# Atari_2006_Dumper.net
KiCad netlist of a schematic drawn in EAGLE
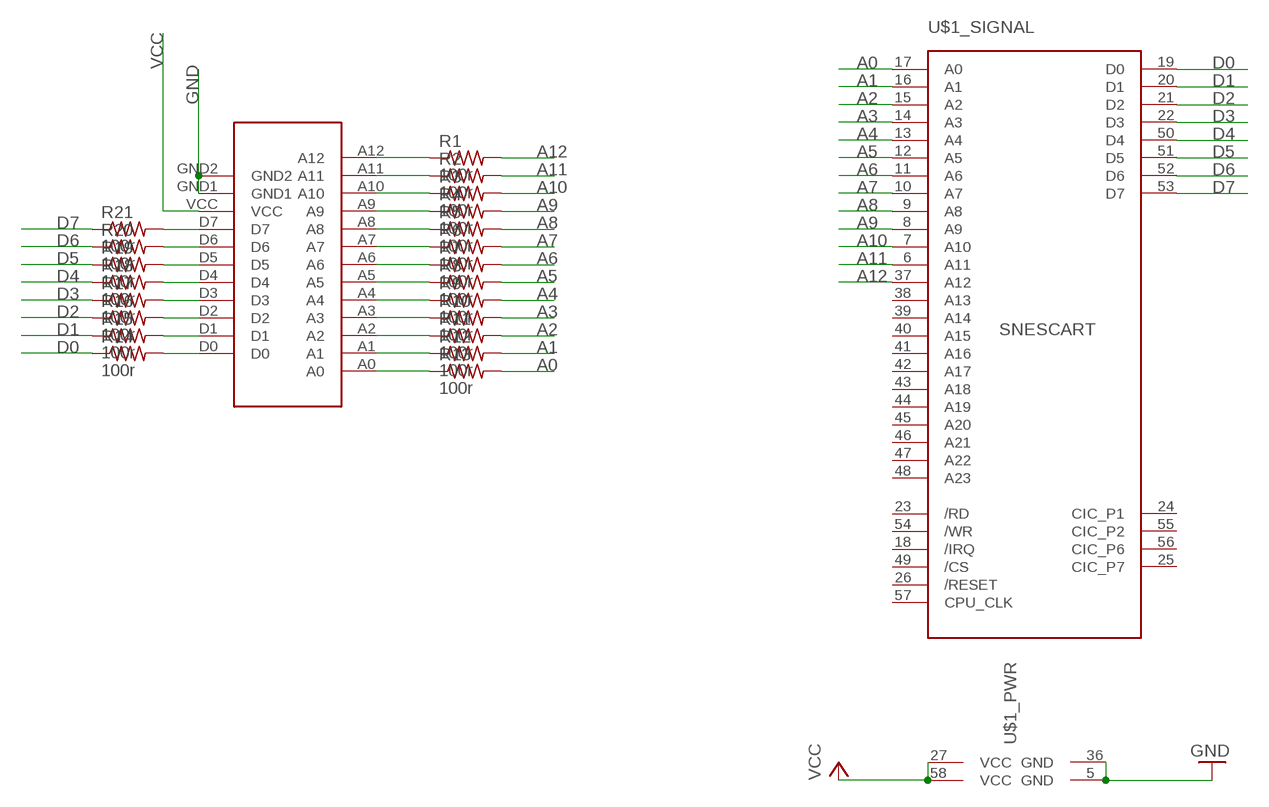
[diagram p0: schematic, sheet 1]

(export (version "E")
  (design (tool "Eeschema 10.0.6"))
  (components
    (comp (ref "R1")
      (value "100r")
      (footprint "eagle-import:R0603")
      (libsource (lib "eagle-import") (part "R-US_R0603"))
    )
    (comp (ref "R2")
      (value "100r")
      (footprint "eagle-import:R0603")
      (libsource (lib "eagle-import") (part "R-US_R0603"))
    )
    (comp (ref "R3")
      (value "100r")
      (footprint "eagle-import:R0603")
      (libsource (lib "eagle-import") (part "R-US_R0603"))
    )
    (comp (ref "R4")
      (value "100r")
      (footprint "eagle-import:R0603")
      (libsource (lib "eagle-import") (part "R-US_R0603"))
    )
    (comp (ref "R5")
      (value "100r")
      (footprint "eagle-import:R0603")
      (libsource (lib "eagle-import") (part "R-US_R0603"))
    )
    (comp (ref "R6")
      (value "100r")
      (footprint "eagle-import:R0603")
      (libsource (lib "eagle-import") (part "R-US_R0603"))
    )
    (comp (ref "R7")
      (value "100r")
      (footprint "eagle-import:R0603")
      (libsource (lib "eagle-import") (part "R-US_R0603"))
    )
    (comp (ref "R8")
      (value "100r")
      (footprint "eagle-import:R0603")
      (libsource (lib "eagle-import") (part "R-US_R0603"))
    )
    (comp (ref "R9")
      (value "100r")
      (footprint "eagle-import:R0603")
      (libsource (lib "eagle-import") (part "R-US_R0603"))
    )
    (comp (ref "R10")
      (value "100r")
      (footprint "eagle-import:R0603")
      (libsource (lib "eagle-import") (part "R-US_R0603"))
    )
    (comp (ref "R11")
      (value "100r")
      (footprint "eagle-import:R0603")
      (libsource (lib "eagle-import") (part "R-US_R0603"))
    )
    (comp (ref "R12")
      (value "100r")
      (footprint "eagle-import:R0603")
      (libsource (lib "eagle-import") (part "R-US_R0603"))
    )
    (comp (ref "R13")
      (value "100r")
      (footprint "eagle-import:R0603")
      (libsource (lib "eagle-import") (part "R-US_R0603"))
    )
    (comp (ref "R14")
      (value "100r")
      (footprint "eagle-import:R0603")
      (libsource (lib "eagle-import") (part "R-US_R0603"))
    )
    (comp (ref "R15")
      (value "100r")
      (footprint "eagle-import:R0603")
      (libsource (lib "eagle-import") (part "R-US_R0603"))
    )
    (comp (ref "R16")
      (value "100r")
      (footprint "eagle-import:R0603")
      (libsource (lib "eagle-import") (part "R-US_R0603"))
    )
    (comp (ref "R17")
      (value "100r")
      (footprint "eagle-import:R0603")
      (libsource (lib "eagle-import") (part "R-US_R0603"))
    )
    (comp (ref "R18")
      (value "100r")
      (footprint "eagle-import:R0603")
      (libsource (lib "eagle-import") (part "R-US_R0603"))
    )
    (comp (ref "R19")
      (value "100r")
      (footprint "eagle-import:R0603")
      (libsource (lib "eagle-import") (part "R-US_R0603"))
    )
    (comp (ref "R20")
      (value "100r")
      (footprint "eagle-import:R0603")
      (libsource (lib "eagle-import") (part "R-US_R0603"))
    )
    (comp (ref "R21")
      (value "100r")
      (footprint "eagle-import:R0603")
      (libsource (lib "eagle-import") (part "R-US_R0603"))
    )
    (comp (ref "U$1")
      (value "SNESCART")
      (footprint "eagle-import:SNESCART")
      (libsource (lib "eagle-import") (part "SNESCART"))
    )
    (comp (ref "U$2")
      (value "2600CARTBIGGERPADS")
      (footprint "eagle-import:2600EDGE-BIGGER")
      (libsource (lib "eagle-import") (part "2600CARTBIGGERPADS"))
    )
  )
  (nets
    (net (code "1") (name "/A0") (class "Default")
      (node (ref "R13") (pin "2") (pinfunction "2_2") (pintype "passive"))
      (node (ref "U$1") (pin "17") (pinfunction "A0_17") (pintype "bidirectional"))
    )
    (net (code "2") (name "/A1") (class "Default")
      (node (ref "R12") (pin "2") (pinfunction "2_2") (pintype "passive"))
      (node (ref "U$1") (pin "16") (pinfunction "A1_16") (pintype "bidirectional"))
    )
    (net (code "3") (name "/A2") (class "Default")
      (node (ref "R11") (pin "2") (pinfunction "2_2") (pintype "passive"))
      (node (ref "U$1") (pin "15") (pinfunction "A2_15") (pintype "bidirectional"))
    )
    (net (code "4") (name "/A3") (class "Default")
      (node (ref "R10") (pin "2") (pinfunction "2_2") (pintype "passive"))
      (node (ref "U$1") (pin "14") (pinfunction "A3_14") (pintype "bidirectional"))
    )
    (net (code "5") (name "/A4") (class "Default")
      (node (ref "R9") (pin "2") (pinfunction "2_2") (pintype "passive"))
      (node (ref "U$1") (pin "13") (pinfunction "A4_13") (pintype "bidirectional"))
    )
    (net (code "6") (name "/A5") (class "Default")
      (node (ref "R8") (pin "2") (pinfunction "2_2") (pintype "passive"))
      (node (ref "U$1") (pin "12") (pinfunction "A5_12") (pintype "bidirectional"))
    )
    (net (code "7") (name "/A6") (class "Default")
      (node (ref "R7") (pin "2") (pinfunction "2_2") (pintype "passive"))
      (node (ref "U$1") (pin "11") (pinfunction "A6_11") (pintype "bidirectional"))
    )
    (net (code "8") (name "/A7") (class "Default")
      (node (ref "R6") (pin "2") (pinfunction "2_2") (pintype "passive"))
      (node (ref "U$1") (pin "10") (pinfunction "A7_10") (pintype "bidirectional"))
    )
    (net (code "9") (name "/A8") (class "Default")
      (node (ref "R5") (pin "2") (pinfunction "2_2") (pintype "passive"))
      (node (ref "U$1") (pin "9") (pinfunction "A8_9") (pintype "bidirectional"))
    )
    (net (code "10") (name "/A9") (class "Default")
      (node (ref "R4") (pin "2") (pinfunction "2_2") (pintype "passive"))
      (node (ref "U$1") (pin "8") (pinfunction "A9_8") (pintype "bidirectional"))
    )
    (net (code "11") (name "/A10") (class "Default")
      (node (ref "R3") (pin "2") (pinfunction "2_2") (pintype "passive"))
      (node (ref "U$1") (pin "7") (pinfunction "A10_7") (pintype "bidirectional"))
    )
    (net (code "12") (name "/A11") (class "Default")
      (node (ref "R2") (pin "2") (pinfunction "2_2") (pintype "passive"))
      (node (ref "U$1") (pin "6") (pinfunction "A11_6") (pintype "bidirectional"))
    )
    (net (code "13") (name "/A12") (class "Default")
      (node (ref "R1") (pin "2") (pinfunction "2_2") (pintype "passive"))
      (node (ref "U$1") (pin "37") (pinfunction "A12_37") (pintype "bidirectional"))
    )
    (net (code "14") (name "/D0") (class "Default")
      (node (ref "R14") (pin "1") (pinfunction "1_1") (pintype "passive"))
      (node (ref "U$1") (pin "19") (pinfunction "D0_19") (pintype "bidirectional"))
    )
    (net (code "15") (name "/D1") (class "Default")
      (node (ref "R15") (pin "1") (pinfunction "1_1") (pintype "passive"))
      (node (ref "U$1") (pin "20") (pinfunction "D1_20") (pintype "bidirectional"))
    )
    (net (code "16") (name "/D2") (class "Default")
      (node (ref "R16") (pin "1") (pinfunction "1_1") (pintype "passive"))
      (node (ref "U$1") (pin "21") (pinfunction "D2_21") (pintype "bidirectional"))
    )
    (net (code "17") (name "/D3") (class "Default")
      (node (ref "R17") (pin "1") (pinfunction "1_1") (pintype "passive"))
      (node (ref "U$1") (pin "22") (pinfunction "D3_22") (pintype "bidirectional"))
    )
    (net (code "18") (name "/D4") (class "Default")
      (node (ref "R18") (pin "1") (pinfunction "1_1") (pintype "passive"))
      (node (ref "U$1") (pin "50") (pinfunction "D4_50") (pintype "bidirectional"))
    )
    (net (code "19") (name "/D5") (class "Default")
      (node (ref "R19") (pin "1") (pinfunction "1_1") (pintype "passive"))
      (node (ref "U$1") (pin "51") (pinfunction "D5_51") (pintype "bidirectional"))
    )
    (net (code "20") (name "/D6") (class "Default")
      (node (ref "R20") (pin "1") (pinfunction "1_1") (pintype "passive"))
      (node (ref "U$1") (pin "52") (pinfunction "D6_52") (pintype "bidirectional"))
    )
    (net (code "21") (name "/D7") (class "Default")
      (node (ref "R21") (pin "1") (pinfunction "1_1") (pintype "passive"))
      (node (ref "U$1") (pin "53") (pinfunction "D7_53") (pintype "bidirectional"))
    )
    (net (code "22") (name "GND") (class "Default")
      (node (ref "U$1") (pin "36") (pinfunction "GND_36") (pintype "power_in"))
      (node (ref "U$1") (pin "5") (pinfunction "GND_5") (pintype "power_in"))
      (node (ref "U$2") (pin "GND1") (pinfunction "GND1_GND1") (pintype "bidirectional"))
      (node (ref "U$2") (pin "GND2") (pinfunction "GND2_GND2") (pintype "bidirectional"))
    )
    (net (code "23") (name "Net-(R1-Pad1)") (class "Default")
      (node (ref "R1") (pin "1") (pinfunction "1_1") (pintype "passive"))
      (node (ref "U$2") (pin "A12") (pinfunction "A12_A12") (pintype "bidirectional"))
    )
    (net (code "24") (name "Net-(R2-Pad1)") (class "Default")
      (node (ref "R2") (pin "1") (pinfunction "1_1") (pintype "passive"))
      (node (ref "U$2") (pin "A11") (pinfunction "A11_A11") (pintype "bidirectional"))
    )
    (net (code "25") (name "Net-(R3-Pad1)") (class "Default")
      (node (ref "R3") (pin "1") (pinfunction "1_1") (pintype "passive"))
      (node (ref "U$2") (pin "A10") (pinfunction "A10_A10") (pintype "bidirectional"))
    )
    (net (code "26") (name "Net-(R4-Pad1)") (class "Default")
      (node (ref "R4") (pin "1") (pinfunction "1_1") (pintype "passive"))
      (node (ref "U$2") (pin "A9") (pinfunction "A9_A9") (pintype "bidirectional"))
    )
    (net (code "27") (name "Net-(R5-Pad1)") (class "Default")
      (node (ref "R5") (pin "1") (pinfunction "1_1") (pintype "passive"))
      (node (ref "U$2") (pin "A8") (pinfunction "A8_A8") (pintype "bidirectional"))
    )
    (net (code "28") (name "Net-(R6-Pad1)") (class "Default")
      (node (ref "R6") (pin "1") (pinfunction "1_1") (pintype "passive"))
      (node (ref "U$2") (pin "A7") (pinfunction "A7_A7") (pintype "bidirectional"))
    )
    (net (code "29") (name "Net-(R7-Pad1)") (class "Default")
      (node (ref "R7") (pin "1") (pinfunction "1_1") (pintype "passive"))
      (node (ref "U$2") (pin "A6") (pinfunction "A6_A6") (pintype "bidirectional"))
    )
    (net (code "30") (name "Net-(R8-Pad1)") (class "Default")
      (node (ref "R8") (pin "1") (pinfunction "1_1") (pintype "passive"))
      (node (ref "U$2") (pin "A5") (pinfunction "A5_A5") (pintype "bidirectional"))
    )
    (net (code "31") (name "Net-(R9-Pad1)") (class "Default")
      (node (ref "R9") (pin "1") (pinfunction "1_1") (pintype "passive"))
      (node (ref "U$2") (pin "A4") (pinfunction "A4_A4") (pintype "bidirectional"))
    )
    (net (code "32") (name "Net-(R10-Pad1)") (class "Default")
      (node (ref "R10") (pin "1") (pinfunction "1_1") (pintype "passive"))
      (node (ref "U$2") (pin "A3") (pinfunction "A3_A3") (pintype "bidirectional"))
    )
    (net (code "33") (name "Net-(R11-Pad1)") (class "Default")
      (node (ref "R11") (pin "1") (pinfunction "1_1") (pintype "passive"))
      (node (ref "U$2") (pin "A2") (pinfunction "A2_A2") (pintype "bidirectional"))
    )
    (net (code "34") (name "Net-(R12-Pad1)") (class "Default")
      (node (ref "R12") (pin "1") (pinfunction "1_1") (pintype "passive"))
      (node (ref "U$2") (pin "A1") (pinfunction "A1_A1") (pintype "bidirectional"))
    )
    (net (code "35") (name "Net-(R13-Pad1)") (class "Default")
      (node (ref "R13") (pin "1") (pinfunction "1_1") (pintype "passive"))
      (node (ref "U$2") (pin "A0") (pinfunction "A0_A0") (pintype "bidirectional"))
    )
    (net (code "36") (name "Net-(R14-Pad2)") (class "Default")
      (node (ref "R14") (pin "2") (pinfunction "2_2") (pintype "passive"))
      (node (ref "U$2") (pin "D0") (pinfunction "D0_D0") (pintype "bidirectional"))
    )
    (net (code "37") (name "Net-(R15-Pad2)") (class "Default")
      (node (ref "R15") (pin "2") (pinfunction "2_2") (pintype "passive"))
      (node (ref "U$2") (pin "D1") (pinfunction "D1_D1") (pintype "bidirectional"))
    )
    (net (code "38") (name "Net-(R16-Pad2)") (class "Default")
      (node (ref "R16") (pin "2") (pinfunction "2_2") (pintype "passive"))
      (node (ref "U$2") (pin "D2") (pinfunction "D2_D2") (pintype "bidirectional"))
    )
    (net (code "39") (name "Net-(R17-Pad2)") (class "Default")
      (node (ref "R17") (pin "2") (pinfunction "2_2") (pintype "passive"))
      (node (ref "U$2") (pin "D3") (pinfunction "D3_D3") (pintype "bidirectional"))
    )
    (net (code "40") (name "Net-(R18-Pad2)") (class "Default")
      (node (ref "R18") (pin "2") (pinfunction "2_2") (pintype "passive"))
      (node (ref "U$2") (pin "D4") (pinfunction "D4_D4") (pintype "bidirectional"))
    )
    (net (code "41") (name "Net-(R19-Pad2)") (class "Default")
      (node (ref "R19") (pin "2") (pinfunction "2_2") (pintype "passive"))
      (node (ref "U$2") (pin "D5") (pinfunction "D5_D5") (pintype "bidirectional"))
    )
    (net (code "42") (name "Net-(R20-Pad2)") (class "Default")
      (node (ref "R20") (pin "2") (pinfunction "2_2") (pintype "passive"))
      (node (ref "U$2") (pin "D6") (pinfunction "D6_D6") (pintype "bidirectional"))
    )
    (net (code "43") (name "Net-(R21-Pad2)") (class "Default")
      (node (ref "R21") (pin "2") (pinfunction "2_2") (pintype "passive"))
      (node (ref "U$2") (pin "D7") (pinfunction "D7_D7") (pintype "bidirectional"))
    )
    (net (code "44") (name "VCC") (class "Default")
      (node (ref "U$1") (pin "27") (pinfunction "VCC_27") (pintype "power_in"))
      (node (ref "U$1") (pin "58") (pinfunction "VCC_58") (pintype "power_in"))
      (node (ref "U$2") (pin "VCC") (pinfunction "VCC_VCC") (pintype "bidirectional"))
    )
    (net (code "45") (name "unconnected-(U$1B-A13-Pad38)") (class "Default")
      (node (ref "U$1") (pin "38") (pinfunction "A13_38") (pintype "bidirectional"))
    )
    (net (code "46") (name "unconnected-(U$1B-A14-Pad39)") (class "Default")
      (node (ref "U$1") (pin "39") (pinfunction "A14_39") (pintype "bidirectional"))
    )
    (net (code "47") (name "unconnected-(U$1B-A15-Pad40)") (class "Default")
      (node (ref "U$1") (pin "40") (pinfunction "A15_40") (pintype "bidirectional"))
    )
    (net (code "48") (name "unconnected-(U$1B-A16-Pad41)") (class "Default")
      (node (ref "U$1") (pin "41") (pinfunction "A16_41") (pintype "bidirectional"))
    )
    (net (code "49") (name "unconnected-(U$1B-A17-Pad42)") (class "Default")
      (node (ref "U$1") (pin "42") (pinfunction "A17_42") (pintype "bidirectional"))
    )
    (net (code "50") (name "unconnected-(U$1B-A18-Pad43)") (class "Default")
      (node (ref "U$1") (pin "43") (pinfunction "A18_43") (pintype "bidirectional"))
    )
    (net (code "51") (name "unconnected-(U$1B-A19-Pad44)") (class "Default")
      (node (ref "U$1") (pin "44") (pinfunction "A19_44") (pintype "bidirectional"))
    )
    (net (code "52") (name "unconnected-(U$1B-A20-Pad45)") (class "Default")
      (node (ref "U$1") (pin "45") (pinfunction "A20_45") (pintype "bidirectional"))
    )
    (net (code "53") (name "unconnected-(U$1B-A21-Pad46)") (class "Default")
      (node (ref "U$1") (pin "46") (pinfunction "A21_46") (pintype "bidirectional"))
    )
    (net (code "54") (name "unconnected-(U$1B-A22-Pad47)") (class "Default")
      (node (ref "U$1") (pin "47") (pinfunction "A22_47") (pintype "bidirectional"))
    )
    (net (code "55") (name "unconnected-(U$1B-A23-Pad48)") (class "Default")
      (node (ref "U$1") (pin "48") (pinfunction "A23_48") (pintype "bidirectional"))
    )
    (net (code "56") (name "unconnected-(U$1B-CIC_P1-Pad24)") (class "Default")
      (node (ref "U$1") (pin "24") (pinfunction "CIC_P1_24") (pintype "bidirectional"))
    )
    (net (code "57") (name "unconnected-(U$1B-CIC_P2-Pad55)") (class "Default")
      (node (ref "U$1") (pin "55") (pinfunction "CIC_P2_55") (pintype "bidirectional"))
    )
    (net (code "58") (name "unconnected-(U$1B-CIC_P6-Pad56)") (class "Default")
      (node (ref "U$1") (pin "56") (pinfunction "CIC_P6_56") (pintype "bidirectional"))
    )
    (net (code "59") (name "unconnected-(U$1B-CIC_P7-Pad25)") (class "Default")
      (node (ref "U$1") (pin "25") (pinfunction "CIC_P7_25") (pintype "bidirectional"))
    )
    (net (code "60") (name "unconnected-(U$1B-CPU_CLK-Pad57)") (class "Default")
      (node (ref "U$1") (pin "57") (pinfunction "CPU_CLK_57") (pintype "bidirectional"))
    )
    (net (code "61") (name "unconnected-(U$1B-{slash}CS-Pad49)") (class "Default")
      (node (ref "U$1") (pin "49") (pinfunction "/CS_49") (pintype "bidirectional"))
    )
    (net (code "62") (name "unconnected-(U$1B-{slash}IRQ-Pad18)") (class "Default")
      (node (ref "U$1") (pin "18") (pinfunction "/IRQ_18") (pintype "bidirectional"))
    )
    (net (code "63") (name "unconnected-(U$1B-{slash}RD-Pad23)") (class "Default")
      (node (ref "U$1") (pin "23") (pinfunction "/RD_23") (pintype "bidirectional"))
    )
    (net (code "64") (name "unconnected-(U$1B-{slash}RESET-Pad26)") (class "Default")
      (node (ref "U$1") (pin "26") (pinfunction "/RESET_26") (pintype "bidirectional"))
    )
    (net (code "65") (name "unconnected-(U$1B-{slash}WR-Pad54)") (class "Default")
      (node (ref "U$1") (pin "54") (pinfunction "/WR_54") (pintype "bidirectional"))
    )
  )
)
